# connection_schema.net
KiCad netlist of a schematic drawn in EAGLE
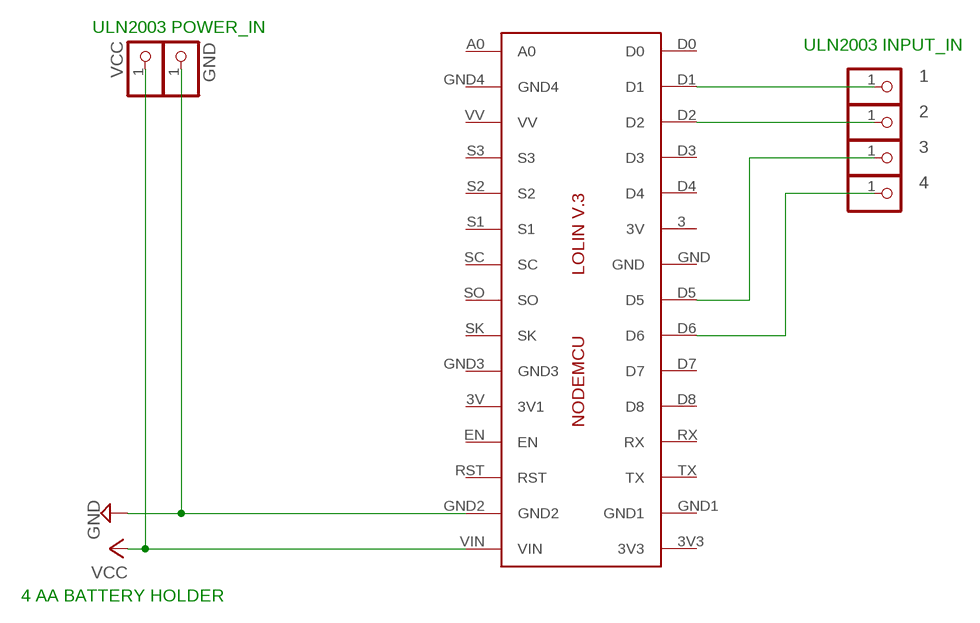
[diagram p0: schematic, sheet 1]

(export (version "E")
  (design (tool "Eeschema 10.0.6"))
  (components
    (comp (ref "1")
      (value "PINHD-1X1")
      (footprint "eagle-import:1X01")
      (libsource (lib "eagle-import") (part "PINHD-1X1"))
    )
    (comp (ref "2")
      (value "PINHD-1X1")
      (footprint "eagle-import:1X01")
      (libsource (lib "eagle-import") (part "PINHD-1X1"))
    )
    (comp (ref "3")
      (value "PINHD-1X1")
      (footprint "eagle-import:1X01")
      (libsource (lib "eagle-import") (part "PINHD-1X1"))
    )
    (comp (ref "4")
      (value "PINHD-1X1")
      (footprint "eagle-import:1X01")
      (libsource (lib "eagle-import") (part "PINHD-1X1"))
    )
    (comp (ref "GND")
      (value "PINHD-1X1")
      (footprint "eagle-import:1X01")
      (libsource (lib "eagle-import") (part "PINHD-1X1"))
    )
    (comp (ref "IC1")
      (value "LOLINV3")
      (footprint "eagle-import:LOLINV3")
      (libsource (lib "eagle-import") (part "LOLINV3"))
    )
    (comp (ref "VCC")
      (value "PINHD-1X1")
      (footprint "eagle-import:1X01")
      (libsource (lib "eagle-import") (part "PINHD-1X1"))
    )
  )
  (nets
    (net (code "1") (name "GND") (class "Default")
      (node (ref "GND") (pin "1") (pinfunction "1_1") (pintype "passive"))
      (node (ref "IC1") (pin "GND2") (pinfunction "GND2_GND2") (pintype "bidirectional"))
    )
    (net (code "2") (name "Net-(1-Pad1)") (class "Default")
      (node (ref "1") (pin "1") (pinfunction "1_1") (pintype "passive"))
      (node (ref "IC1") (pin "D1") (pinfunction "D1_D1") (pintype "bidirectional"))
    )
    (net (code "3") (name "Net-(2-Pad1)") (class "Default")
      (node (ref "2") (pin "1") (pinfunction "1_1") (pintype "passive"))
      (node (ref "IC1") (pin "D2") (pinfunction "D2_D2") (pintype "bidirectional"))
    )
    (net (code "4") (name "Net-(3-Pad1)") (class "Default")
      (node (ref "3") (pin "1") (pinfunction "1_1") (pintype "passive"))
      (node (ref "IC1") (pin "D5") (pinfunction "D5_D5") (pintype "bidirectional"))
    )
    (net (code "5") (name "Net-(4-Pad1)") (class "Default")
      (node (ref "4") (pin "1") (pinfunction "1_1") (pintype "passive"))
      (node (ref "IC1") (pin "D6") (pinfunction "D6_D6") (pintype "bidirectional"))
    )
    (net (code "6") (name "VCC") (class "Default")
      (node (ref "IC1") (pin "VIN") (pinfunction "VIN_VIN") (pintype "bidirectional"))
      (node (ref "VCC") (pin "1") (pinfunction "1_1") (pintype "passive"))
    )
    (net (code "7") (name "unconnected-(IC1-3V-Pad3)") (class "Default")
      (node (ref "IC1") (pin "3") (pinfunction "3V_3") (pintype "bidirectional"))
    )
    (net (code "8") (name "unconnected-(IC1-3V1-Pad3V)") (class "Default")
      (node (ref "IC1") (pin "3V") (pinfunction "3V1_3V") (pintype "bidirectional"))
    )
    (net (code "9") (name "unconnected-(IC1-Pad3V3)") (class "Default")
      (node (ref "IC1") (pin "3V3") (pinfunction "3V3_3V3") (pintype "bidirectional"))
    )
    (net (code "10") (name "unconnected-(IC1-PadA0)") (class "Default")
      (node (ref "IC1") (pin "A0") (pinfunction "A0_A0") (pintype "bidirectional"))
    )
    (net (code "11") (name "unconnected-(IC1-PadD0)") (class "Default")
      (node (ref "IC1") (pin "D0") (pinfunction "D0_D0") (pintype "bidirectional"))
    )
    (net (code "12") (name "unconnected-(IC1-PadD3)") (class "Default")
      (node (ref "IC1") (pin "D3") (pinfunction "D3_D3") (pintype "bidirectional"))
    )
    (net (code "13") (name "unconnected-(IC1-PadD4)") (class "Default")
      (node (ref "IC1") (pin "D4") (pinfunction "D4_D4") (pintype "bidirectional"))
    )
    (net (code "14") (name "unconnected-(IC1-PadD7)") (class "Default")
      (node (ref "IC1") (pin "D7") (pinfunction "D7_D7") (pintype "bidirectional"))
    )
    (net (code "15") (name "unconnected-(IC1-PadD8)") (class "Default")
      (node (ref "IC1") (pin "D8") (pinfunction "D8_D8") (pintype "bidirectional"))
    )
    (net (code "16") (name "unconnected-(IC1-PadEN)") (class "Default")
      (node (ref "IC1") (pin "EN") (pinfunction "EN_EN") (pintype "bidirectional"))
    )
    (net (code "17") (name "unconnected-(IC1-PadGND)") (class "Default")
      (node (ref "IC1") (pin "GND") (pinfunction "GND_GND") (pintype "bidirectional"))
    )
    (net (code "18") (name "unconnected-(IC1-PadGND1)") (class "Default")
      (node (ref "IC1") (pin "GND1") (pinfunction "GND1_GND1") (pintype "bidirectional"))
    )
    (net (code "19") (name "unconnected-(IC1-PadGND3)") (class "Default")
      (node (ref "IC1") (pin "GND3") (pinfunction "GND3_GND3") (pintype "bidirectional"))
    )
    (net (code "20") (name "unconnected-(IC1-PadGND4)") (class "Default")
      (node (ref "IC1") (pin "GND4") (pinfunction "GND4_GND4") (pintype "bidirectional"))
    )
    (net (code "21") (name "unconnected-(IC1-PadRST)") (class "Default")
      (node (ref "IC1") (pin "RST") (pinfunction "RST_RST") (pintype "bidirectional"))
    )
    (net (code "22") (name "unconnected-(IC1-PadRX)") (class "Default")
      (node (ref "IC1") (pin "RX") (pinfunction "RX_RX") (pintype "bidirectional"))
    )
    (net (code "23") (name "unconnected-(IC1-PadS1)") (class "Default")
      (node (ref "IC1") (pin "S1") (pinfunction "S1_S1") (pintype "bidirectional"))
    )
    (net (code "24") (name "unconnected-(IC1-PadS2)") (class "Default")
      (node (ref "IC1") (pin "S2") (pinfunction "S2_S2") (pintype "bidirectional"))
    )
    (net (code "25") (name "unconnected-(IC1-PadS3)") (class "Default")
      (node (ref "IC1") (pin "S3") (pinfunction "S3_S3") (pintype "bidirectional"))
    )
    (net (code "26") (name "unconnected-(IC1-PadSC)") (class "Default")
      (node (ref "IC1") (pin "SC") (pinfunction "SC_SC") (pintype "bidirectional"))
    )
    (net (code "27") (name "unconnected-(IC1-PadSK)") (class "Default")
      (node (ref "IC1") (pin "SK") (pinfunction "SK_SK") (pintype "bidirectional"))
    )
    (net (code "28") (name "unconnected-(IC1-PadSO)") (class "Default")
      (node (ref "IC1") (pin "SO") (pinfunction "SO_SO") (pintype "bidirectional"))
    )
    (net (code "29") (name "unconnected-(IC1-PadTX)") (class "Default")
      (node (ref "IC1") (pin "TX") (pinfunction "TX_TX") (pintype "bidirectional"))
    )
    (net (code "30") (name "unconnected-(IC1-PadVV)") (class "Default")
      (node (ref "IC1") (pin "VV") (pinfunction "VV_VV") (pintype "bidirectional"))
    )
  )
)
